# HUP.net
KiCad netlist of a schematic drawn in Altium Designer
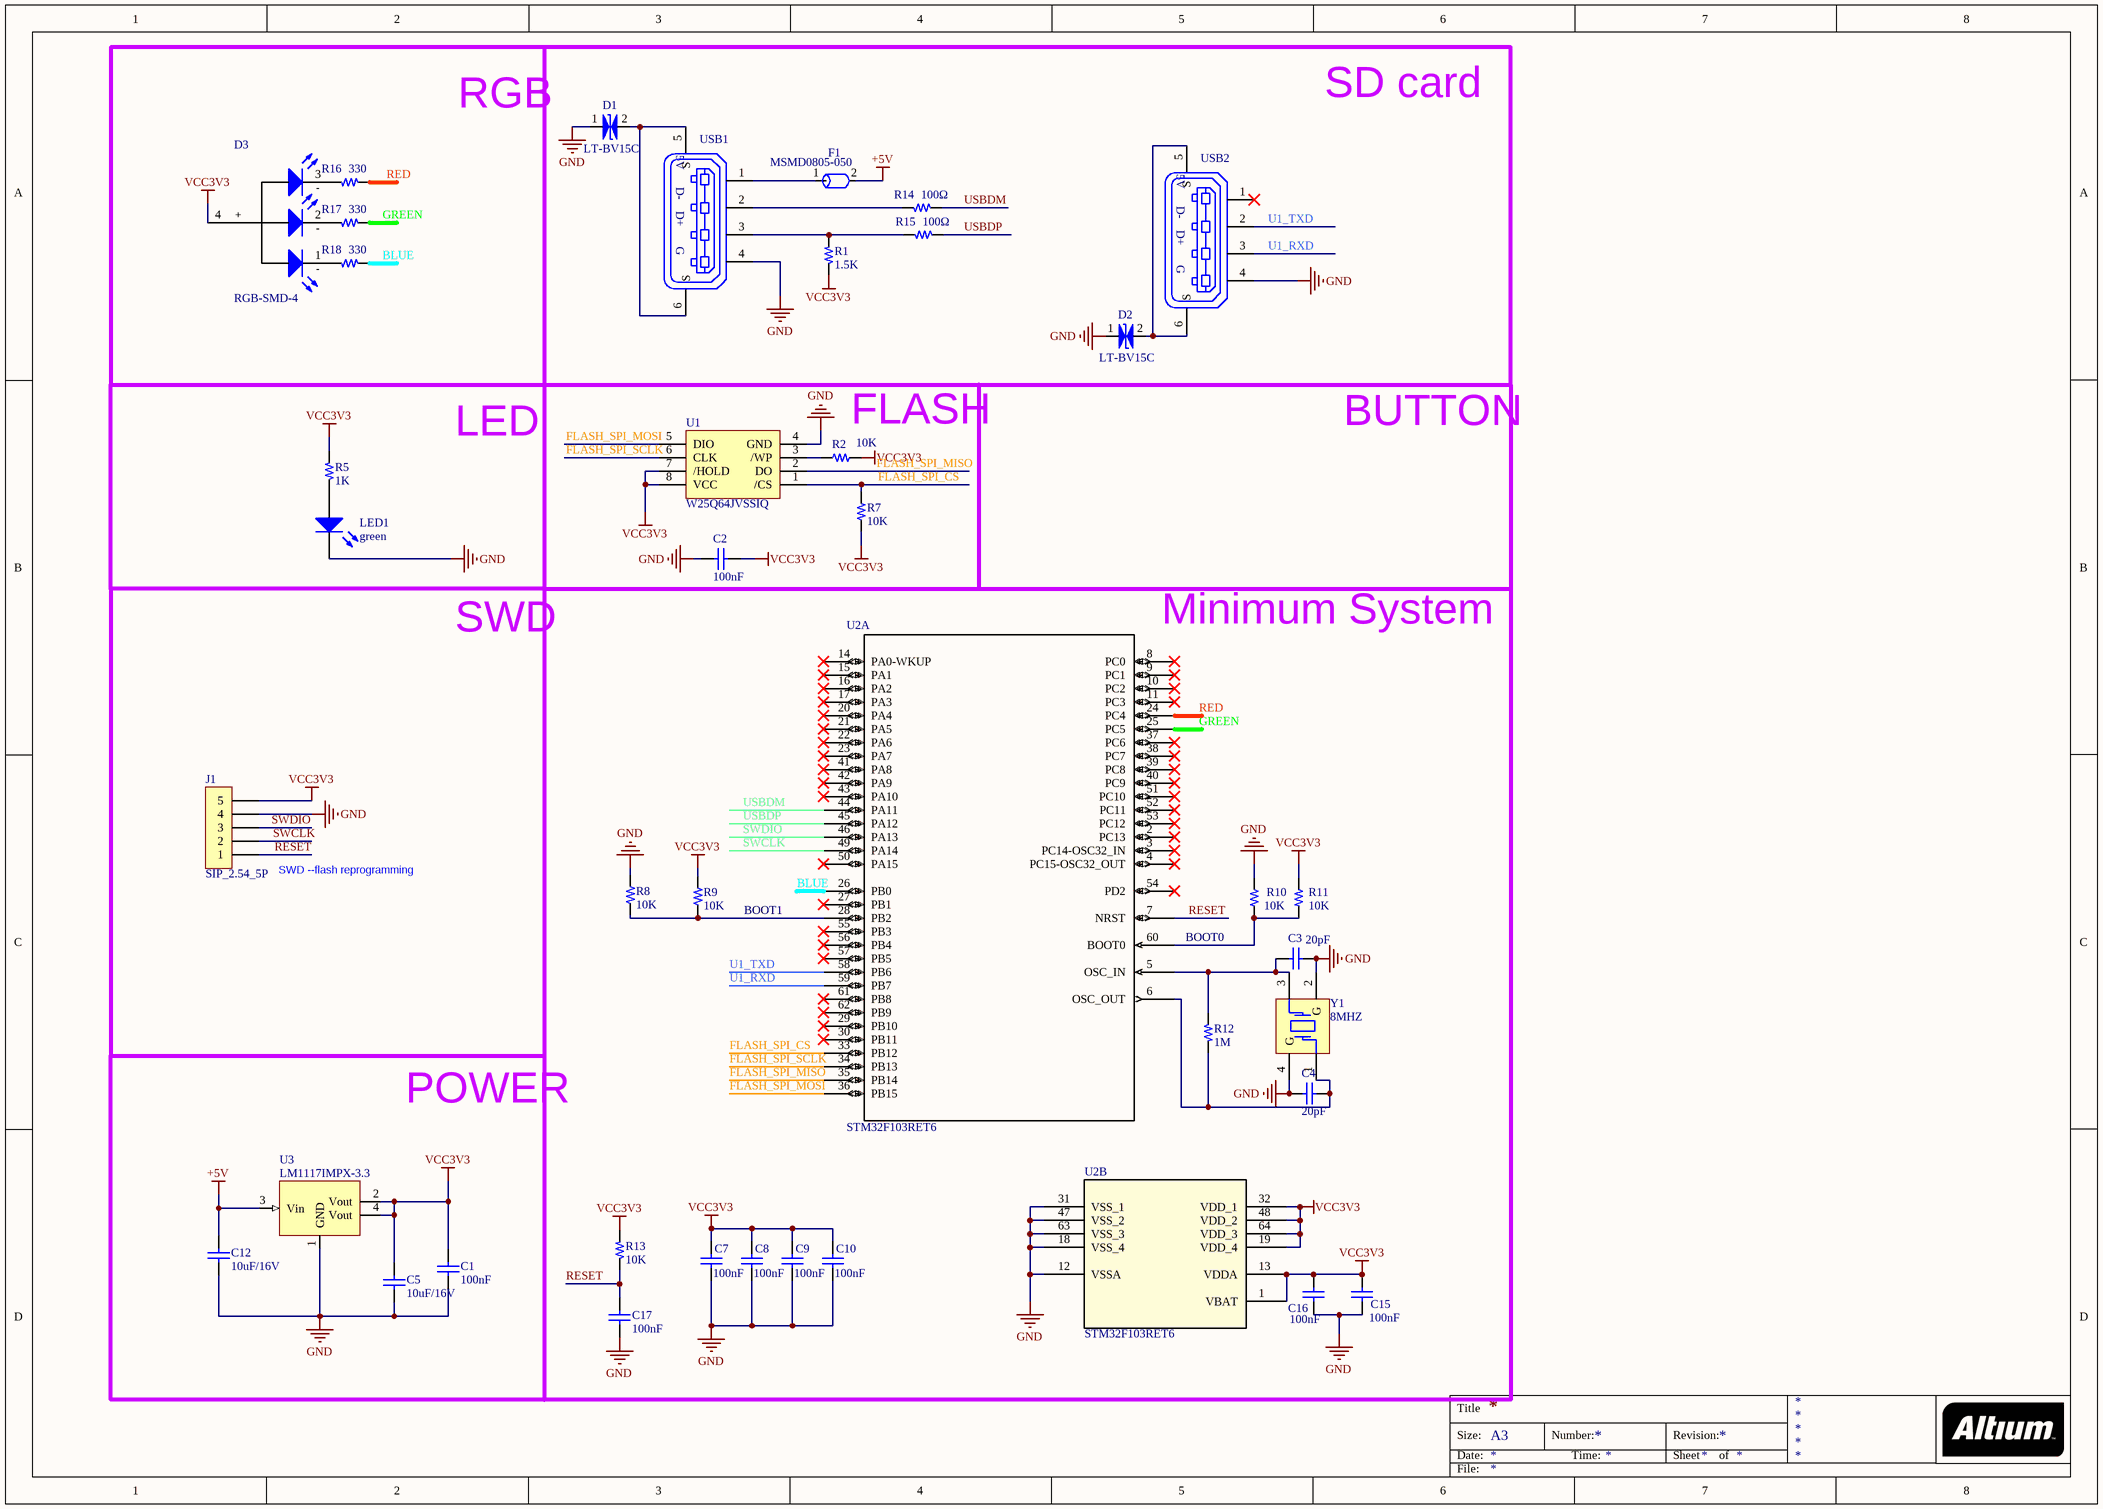
[diagram p0: HUP.SchDoc]

(export (version "E")
  (design (tool "Eeschema 10.0.6"))
  (components
    (comp (ref "C1") (value "100nF") (footprint "C-0603") (libsource (lib "电容") (part "100nF_0805")))
    (comp (ref "C2") (value "100nF") (footprint "C-0603") (libsource (lib "电容") (part "100nF_0805")))
    (comp (ref "C3") (value "20pF") (footprint "C-0603") (libsource (lib "电容") (part "20pF_0805")))
    (comp (ref "C4") (value "20pF") (footprint "C-0603") (libsource (lib "电容") (part "20pF_0805")))
    (comp (ref "C5") (value "10uF/16V") (footprint "C-0603") (libsource (lib "电容") (part "10uF_0805")))
    (comp (ref "C7") (value "100nF") (footprint "C-0603") (libsource (lib "电容") (part "100nF_0805")))
    (comp (ref "C8") (value "100nF") (footprint "C-0603") (libsource (lib "电容") (part "100nF_0805")))
    (comp (ref "C9") (value "100nF") (footprint "C-0603") (libsource (lib "电容") (part "100nF_0805")))
    (comp (ref "C10") (value "100nF") (footprint "C-0603") (libsource (lib "电容") (part "100nF_0805")))
    (comp (ref "C12") (value "10uF/16V") (footprint "C-0603") (libsource (lib "电容") (part "10uF_0805")))
    (comp (ref "C15") (value "100nF") (footprint "C-0603") (libsource (lib "电容") (part "1uF_0805")))
    (comp (ref "C16") (value "100nF") (footprint "C-0603") (libsource (lib "电容") (part "10nF_0805")))
    (comp (ref "C17") (value "100nF") (footprint "C-0603") (libsource (lib "电容") (part "20pF_0805")))
    (comp (ref "D1") (value "LT-BV15C") (footprint "SOD323T") (libsource (lib "临时库") (part "LTBV05C")))
    (comp (ref "D2") (value "LT-BV15C") (footprint "SOD323T") (libsource (lib "临时库") (part "LTBV05C")))
    (comp (ref "D3") (value "RGB-SMD-4") (libsource (lib "Schlib1") (part "RGB")))
    (comp (ref "F1")
      (value "MSMD0805-050")
      (footprint "R0805")
      (libsource (lib "其它") (part "FB_1K/500mA_0805"))
    )
    (comp (ref "J1")
      (value "SIP_2.54_5P")
      (footprint "SIP_2.54_5P")
      (libsource (lib "connectors") (part "SIP_2.54_5P"))
    )
    (comp (ref "LED1") (value "green") (footprint "0603_LED_S1") (libsource (lib "HHFNC") (part "LED1")))
    (comp (ref "R1") (value "1.5K") (footprint "R-0603") (libsource (lib "电阻") (part "10K±1%_0805")))
    (comp (ref "R2") (value "10K") (footprint "R-0603") (libsource (lib "电阻") (part "4.7K±1%_0805")))
    (comp (ref "R5") (value "1K") (footprint "R-0603") (libsource (lib "电阻") (part "1K±1%_0805")))
    (comp (ref "R7") (value "10K") (footprint "R-0603") (libsource (lib "电阻") (part "4.7K±1%_0805")))
    (comp (ref "R8") (value "10K") (footprint "R-0603") (libsource (lib "电阻") (part "10K±1%_0805")))
    (comp (ref "R9") (value "10K") (footprint "R-0603") (libsource (lib "电阻") (part "10K±1%_0805")))
    (comp (ref "R10") (value "10K") (footprint "R-0603") (libsource (lib "电阻") (part "10K±1%_0805")))
    (comp (ref "R11") (value "10K") (footprint "R-0603") (libsource (lib "电阻") (part "10K±1%_0805")))
    (comp (ref "R12") (value "1M") (footprint "R-0603") (libsource (lib "电阻") (part "1M±1%_0805")))
    (comp (ref "R13") (value "10K") (footprint "R-0603") (libsource (lib "电阻") (part "10K±1%_0805")))
    (comp (ref "R14") (value "100Ω") (footprint "R-0603") (libsource (lib "电阻") (part "10K±1%_0805")))
    (comp (ref "R15") (value "100Ω") (footprint "R-0603") (libsource (lib "电阻") (part "10K±1%_0805")))
    (comp (ref "R16") (value "330") (footprint "R-0603") (libsource (lib "电阻") (part "10K±1%_0805")))
    (comp (ref "R17") (value "330") (footprint "R-0603") (libsource (lib "电阻") (part "10K±1%_0805")))
    (comp (ref "R18") (value "330") (footprint "R-0603") (libsource (lib "电阻") (part "10K±1%_0805")))
    (comp (ref "U1")
      (value "W25Q64JVSSIQ")
      (footprint "W25Q64JVSSIQ")
      (libsource (lib "双水平_2") (part "W25Q64JVSSIQ"))
    )
    (comp (ref "U2")
      (value "STM32F103RET6")
      (footprint "LQFP64-10x10mm")
      (description "Imported")
      (fields
        (field (name "MANUFACTURER_PART_NUMBER") "stm32f10xrxt2")
        (field (name "COPYRIGHT") "Copyright (C) 2016 Accelerated Designs. All rights reserved")
      )
      (libsource (lib "2019-01-10_14-16-15") (part "STM32F10xRxT2"))
    )
    (comp (ref "U3")
      (value "LM1117IMPX-3.3")
      (footprint "SOT223")
      (libsource (lib "BLDC_SchLib") (part "LM1117IMPX-3.3"))
    )
    (comp (ref "USB1") (value "USB") (footprint "USB-A-Plug-2") (libsource (lib "双水平_2") (part "USB_A")))
    (comp (ref "USB2") (value "USB") (footprint "USB A Header") (libsource (lib "双水平_2") (part "USB_A")))
    (comp (ref "Y1") (value "8MHZ") (footprint "TAS3225") (libsource (lib "my") (part "泰艺5032晶振8MHz")))
  )
  (nets
    (net (code "1") (name "+5V") (class "Default")
      (node (ref "C12") (pin "1") (pinfunction "1_1") (pintype "passive"))
      (node (ref "F1") (pin "2") (pinfunction "2_2") (pintype "passive"))
      (node (ref "U3") (pin "3") (pinfunction "Vin_3") (pintype "input"))
    )
    (net (code "2") (name "/BLUE") (class "Default")
      (node (ref "R18") (pin "1") (pinfunction "TOP_1") (pintype "passive"))
      (node (ref "U2") (pin "26") (pinfunction "PB0_26") (pintype "bidirectional"))
    )
    (net (code "3") (name "/BOOT0") (class "Default")
      (node (ref "R10") (pin "2") (pinfunction "BOT_2") (pintype "passive"))
      (node (ref "R11") (pin "2") (pinfunction "BOT_2") (pintype "passive"))
      (node (ref "U2") (pin "60") (pinfunction "BOOT0_60") (pintype "input"))
    )
    (net (code "4") (name "/BOOT1") (class "Default")
      (node (ref "R8") (pin "2") (pinfunction "BOT_2") (pintype "passive"))
      (node (ref "R9") (pin "2") (pinfunction "BOT_2") (pintype "passive"))
      (node (ref "U2") (pin "28") (pinfunction "PB2_28") (pintype "bidirectional"))
    )
    (net (code "5") (name "/FLASH_SPI_CS") (class "Default")
      (node (ref "R7") (pin "2") (pinfunction "BOT_2") (pintype "passive"))
      (node (ref "U1") (pin "1") (pinfunction "/CS_1") (pintype "passive"))
      (node (ref "U2") (pin "33") (pinfunction "PB12_33") (pintype "bidirectional"))
    )
    (net (code "6") (name "/FLASH_SPI_MISO") (class "Default")
      (node (ref "U1") (pin "2") (pinfunction "DO_2") (pintype "passive"))
      (node (ref "U2") (pin "35") (pinfunction "PB14_35") (pintype "bidirectional"))
    )
    (net (code "7") (name "/FLASH_SPI_MOSI") (class "Default")
      (node (ref "U1") (pin "5") (pinfunction "DIO_5") (pintype "passive"))
      (node (ref "U2") (pin "36") (pinfunction "PB15_36") (pintype "bidirectional"))
    )
    (net (code "8") (name "/FLASH_SPI_SCLK") (class "Default")
      (node (ref "U1") (pin "6") (pinfunction "CLK_6") (pintype "passive"))
      (node (ref "U2") (pin "34") (pinfunction "PB13_34") (pintype "bidirectional"))
    )
    (net (code "9") (name "/GREEN") (class "Default")
      (node (ref "R17") (pin "1") (pinfunction "TOP_1") (pintype "passive"))
      (node (ref "U2") (pin "25") (pinfunction "PC5_25") (pintype "bidirectional"))
    )
    (net (code "10") (name "/RED") (class "Default")
      (node (ref "R16") (pin "1") (pinfunction "TOP_1") (pintype "passive"))
      (node (ref "U2") (pin "24") (pinfunction "PC4_24") (pintype "bidirectional"))
    )
    (net (code "11") (name "/RESET") (class "Default")
      (node (ref "C17") (pin "1") (pinfunction "1_1") (pintype "passive"))
      (node (ref "J1") (pin "1") (pinfunction "1_1") (pintype "passive"))
      (node (ref "R13") (pin "1") (pinfunction "TOP_1") (pintype "passive"))
      (node (ref "U2") (pin "7") (pinfunction "NRST_7") (pintype "bidirectional"))
    )
    (net (code "12") (name "/SWCLK") (class "Default")
      (node (ref "J1") (pin "2") (pinfunction "2_2") (pintype "passive"))
      (node (ref "U2") (pin "49") (pinfunction "PA14_49") (pintype "bidirectional"))
    )
    (net (code "13") (name "/SWDIO") (class "Default")
      (node (ref "J1") (pin "3") (pinfunction "3_3") (pintype "passive"))
      (node (ref "U2") (pin "46") (pinfunction "PA13_46") (pintype "bidirectional"))
    )
    (net (code "14") (name "/U1_RXD") (class "Default")
      (node (ref "U2") (pin "59") (pinfunction "PB7_59") (pintype "bidirectional"))
      (node (ref "USB2") (pin "3") (pinfunction "3_3") (pintype "passive"))
    )
    (net (code "15") (name "/U1_TXD") (class "Default")
      (node (ref "U2") (pin "58") (pinfunction "PB6_58") (pintype "bidirectional"))
      (node (ref "USB2") (pin "2") (pinfunction "2_2") (pintype "passive"))
    )
    (net (code "16") (name "/USBDM") (class "Default")
      (node (ref "R14") (pin "1") (pinfunction "TOP_1") (pintype "passive"))
      (node (ref "U2") (pin "44") (pinfunction "PA11_44") (pintype "bidirectional"))
    )
    (net (code "17") (name "/USBDP") (class "Default")
      (node (ref "R15") (pin "1") (pinfunction "TOP_1") (pintype "passive"))
      (node (ref "U2") (pin "45") (pinfunction "PA12_45") (pintype "bidirectional"))
    )
    (net (code "18") (name "GND") (class "Default")
      (node (ref "C1") (pin "1") (pinfunction "1_1") (pintype "passive"))
      (node (ref "C10") (pin "1") (pinfunction "1_1") (pintype "passive"))
      (node (ref "C12") (pin "2") (pinfunction "2_2") (pintype "passive"))
      (node (ref "C15") (pin "2") (pinfunction "2_2") (pintype "passive"))
      (node (ref "C16") (pin "1") (pinfunction "1_1") (pintype "passive"))
      (node (ref "C17") (pin "2") (pinfunction "2_2") (pintype "passive"))
      (node (ref "C2") (pin "2") (pinfunction "2_2") (pintype "passive"))
      (node (ref "C3") (pin "1") (pinfunction "1_1") (pintype "passive"))
      (node (ref "C4") (pin "2") (pinfunction "2_2") (pintype "passive"))
      (node (ref "C5") (pin "2") (pinfunction "2_2") (pintype "passive"))
      (node (ref "C7") (pin "1") (pinfunction "1_1") (pintype "passive"))
      (node (ref "C8") (pin "1") (pinfunction "1_1") (pintype "passive"))
      (node (ref "C9") (pin "1") (pinfunction "1_1") (pintype "passive"))
      (node (ref "D1") (pin "1") (pinfunction "1_1") (pintype "passive"))
      (node (ref "D2") (pin "1") (pinfunction "1_1") (pintype "passive"))
      (node (ref "J1") (pin "4") (pinfunction "4_4") (pintype "passive"))
      (node (ref "LED1") (pin "2") (pinfunction "K_2") (pintype "passive"))
      (node (ref "R10") (pin "1") (pinfunction "TOP_1") (pintype "passive"))
      (node (ref "R8") (pin "1") (pinfunction "TOP_1") (pintype "passive"))
      (node (ref "U1") (pin "4") (pinfunction "GND_4") (pintype "passive"))
      (node (ref "U2") (pin "12") (pinfunction "VSSA_12") (pintype "power_in"))
      (node (ref "U2") (pin "18") (pinfunction "VSS_4_18") (pintype "power_in"))
      (node (ref "U2") (pin "31") (pinfunction "VSS_1_31") (pintype "power_in"))
      (node (ref "U2") (pin "47") (pinfunction "VSS_2_47") (pintype "power_in"))
      (node (ref "U2") (pin "63") (pinfunction "VSS_3_63") (pintype "power_in"))
      (node (ref "U3") (pin "1") (pinfunction "GND_1") (pintype "passive"))
      (node (ref "USB1") (pin "4") (pinfunction "4_4") (pintype "passive"))
      (node (ref "USB2") (pin "4") (pinfunction "4_4") (pintype "passive"))
      (node (ref "Y1") (pin "2") (pinfunction "G_2") (pintype "passive"))
      (node (ref "Y1") (pin "4") (pinfunction "G_4") (pintype "passive"))
    )
    (net (code "19") (name "Net-(D1-Pad2)") (class "Default")
      (node (ref "D1") (pin "2") (pinfunction "2_2") (pintype "passive"))
      (node (ref "USB1") (pin "5") (pinfunction "S_5") (pintype "passive"))
      (node (ref "USB1") (pin "6") (pinfunction "S_6") (pintype "passive"))
    )
    (net (code "20") (name "Net-(D2-Pad2)") (class "Default")
      (node (ref "D2") (pin "2") (pinfunction "2_2") (pintype "passive"))
      (node (ref "USB2") (pin "5") (pinfunction "S_5") (pintype "passive"))
      (node (ref "USB2") (pin "6") (pinfunction "S_6") (pintype "passive"))
    )
    (net (code "21") (name "Net-(F1-Pad1)") (class "Default")
      (node (ref "F1") (pin "1") (pinfunction "1_1") (pintype "passive"))
      (node (ref "USB1") (pin "1") (pinfunction "1_1") (pintype "passive"))
    )
    (net (code "22") (name "Net-(LED1-A)") (class "Default")
      (node (ref "LED1") (pin "1") (pinfunction "A_1") (pintype "passive"))
      (node (ref "R5") (pin "1") (pinfunction "TOP_1") (pintype "passive"))
    )
    (net (code "23") (name "Net-(R1-BOT)") (class "Default")
      (node (ref "R1") (pin "2") (pinfunction "BOT_2") (pintype "passive"))
      (node (ref "R15") (pin "2") (pinfunction "BOT_2") (pintype "passive"))
      (node (ref "USB1") (pin "3") (pinfunction "3_3") (pintype "passive"))
    )
    (net (code "24") (name "Net-(R2-BOT)") (class "Default")
      (node (ref "R2") (pin "2") (pinfunction "BOT_2") (pintype "passive"))
      (node (ref "U1") (pin "3") (pinfunction "/WP_3") (pintype "passive"))
    )
    (net (code "25") (name "Net-(R12-BOT)") (class "Default")
      (node (ref "C3") (pin "2") (pinfunction "2_2") (pintype "passive"))
      (node (ref "R12") (pin "2") (pinfunction "BOT_2") (pintype "passive"))
      (node (ref "U2") (pin "5") (pinfunction "OSC_IN_5") (pintype "input"))
      (node (ref "Y1") (pin "3") (pinfunction "3_3") (pintype "passive"))
    )
    (net (code "26") (name "Net-(R12-TOP)") (class "Default")
      (node (ref "C4") (pin "1") (pinfunction "1_1") (pintype "passive"))
      (node (ref "R12") (pin "1") (pinfunction "TOP_1") (pintype "passive"))
      (node (ref "U2") (pin "6") (pinfunction "OSC_OUT_6") (pintype "output"))
      (node (ref "Y1") (pin "1") (pinfunction "1_1") (pintype "passive"))
    )
    (net (code "27") (name "Net-(R14-BOT)") (class "Default")
      (node (ref "R14") (pin "2") (pinfunction "BOT_2") (pintype "passive"))
      (node (ref "USB1") (pin "2") (pinfunction "2_2") (pintype "passive"))
    )
    (net (code "28") (name "Net-(R16-BOT)") (class "Default")
      (node (ref "D3") (pin "3") (pinfunction "3_3") (pintype "passive"))
      (node (ref "R16") (pin "2") (pinfunction "BOT_2") (pintype "passive"))
    )
    (net (code "29") (name "Net-(R17-BOT)") (class "Default")
      (node (ref "D3") (pin "2") (pinfunction "2_2") (pintype "passive"))
      (node (ref "R17") (pin "2") (pinfunction "BOT_2") (pintype "passive"))
    )
    (net (code "30") (name "Net-(R18-BOT)") (class "Default")
      (node (ref "D3") (pin "1") (pinfunction "1_1") (pintype "passive"))
      (node (ref "R18") (pin "2") (pinfunction "BOT_2") (pintype "passive"))
    )
    (net (code "31") (name "VCC3V3") (class "Default")
      (node (ref "C1") (pin "2") (pinfunction "2_2") (pintype "passive"))
      (node (ref "C10") (pin "2") (pinfunction "2_2") (pintype "passive"))
      (node (ref "C15") (pin "1") (pinfunction "1_1") (pintype "passive"))
      (node (ref "C16") (pin "2") (pinfunction "2_2") (pintype "passive"))
      (node (ref "C2") (pin "1") (pinfunction "1_1") (pintype "passive"))
      (node (ref "C5") (pin "1") (pinfunction "1_1") (pintype "passive"))
      (node (ref "C7") (pin "2") (pinfunction "2_2") (pintype "passive"))
      (node (ref "C8") (pin "2") (pinfunction "2_2") (pintype "passive"))
      (node (ref "C9") (pin "2") (pinfunction "2_2") (pintype "passive"))
      (node (ref "D3") (pin "4") (pinfunction "4_4") (pintype "passive"))
      (node (ref "J1") (pin "5") (pinfunction "5_5") (pintype "passive"))
      (node (ref "R1") (pin "1") (pinfunction "TOP_1") (pintype "passive"))
      (node (ref "R11") (pin "1") (pinfunction "TOP_1") (pintype "passive"))
      (node (ref "R13") (pin "2") (pinfunction "BOT_2") (pintype "passive"))
      (node (ref "R2") (pin "1") (pinfunction "TOP_1") (pintype "passive"))
      (node (ref "R5") (pin "2") (pinfunction "BOT_2") (pintype "passive"))
      (node (ref "R7") (pin "1") (pinfunction "TOP_1") (pintype "passive"))
      (node (ref "R9") (pin "1") (pinfunction "TOP_1") (pintype "passive"))
      (node (ref "U1") (pin "7") (pinfunction "/HOLD_7") (pintype "passive"))
      (node (ref "U1") (pin "8") (pinfunction "VCC_8") (pintype "passive"))
      (node (ref "U2") (pin "1") (pinfunction "VBAT_1") (pintype "power_in"))
      (node (ref "U2") (pin "13") (pinfunction "VDDA_13") (pintype "power_in"))
      (node (ref "U2") (pin "19") (pinfunction "VDD_4_19") (pintype "power_in"))
      (node (ref "U2") (pin "32") (pinfunction "VDD_1_32") (pintype "power_in"))
      (node (ref "U2") (pin "48") (pinfunction "VDD_2_48") (pintype "power_in"))
      (node (ref "U2") (pin "64") (pinfunction "VDD_3_64") (pintype "power_in"))
      (node (ref "U3") (pin "2") (pinfunction "Vout_2") (pintype "passive"))
      (node (ref "U3") (pin "4") (pinfunction "Vout_4") (pintype "passive"))
    )
    (net (code "32") (name "unconnected-(U2A-PA0-WKUP-Pad14)") (class "Default")
      (node (ref "U2") (pin "14") (pinfunction "PA0-WKUP_14") (pintype "bidirectional+no_connect"))
    )
    (net (code "33") (name "unconnected-(U2A-PA1-Pad15)") (class "Default")
      (node (ref "U2") (pin "15") (pinfunction "PA1_15") (pintype "bidirectional+no_connect"))
    )
    (net (code "34") (name "unconnected-(U2A-PA2-Pad16)") (class "Default")
      (node (ref "U2") (pin "16") (pinfunction "PA2_16") (pintype "bidirectional+no_connect"))
    )
    (net (code "35") (name "unconnected-(U2A-PA3-Pad17)") (class "Default")
      (node (ref "U2") (pin "17") (pinfunction "PA3_17") (pintype "bidirectional+no_connect"))
    )
    (net (code "36") (name "unconnected-(U2A-PA4-Pad20)") (class "Default")
      (node (ref "U2") (pin "20") (pinfunction "PA4_20") (pintype "bidirectional+no_connect"))
    )
    (net (code "37") (name "unconnected-(U2A-PA5-Pad21)") (class "Default")
      (node (ref "U2") (pin "21") (pinfunction "PA5_21") (pintype "bidirectional+no_connect"))
    )
    (net (code "38") (name "unconnected-(U2A-PA6-Pad22)") (class "Default")
      (node (ref "U2") (pin "22") (pinfunction "PA6_22") (pintype "bidirectional+no_connect"))
    )
    (net (code "39") (name "unconnected-(U2A-PA7-Pad23)") (class "Default")
      (node (ref "U2") (pin "23") (pinfunction "PA7_23") (pintype "bidirectional+no_connect"))
    )
    (net (code "40") (name "unconnected-(U2A-PA8-Pad41)") (class "Default")
      (node (ref "U2") (pin "41") (pinfunction "PA8_41") (pintype "bidirectional+no_connect"))
    )
    (net (code "41") (name "unconnected-(U2A-PA9-Pad42)") (class "Default")
      (node (ref "U2") (pin "42") (pinfunction "PA9_42") (pintype "bidirectional+no_connect"))
    )
    (net (code "42") (name "unconnected-(U2A-PA10-Pad43)") (class "Default")
      (node (ref "U2") (pin "43") (pinfunction "PA10_43") (pintype "bidirectional+no_connect"))
    )
    (net (code "43") (name "unconnected-(U2A-PA15-Pad50)") (class "Default")
      (node (ref "U2") (pin "50") (pinfunction "PA15_50") (pintype "bidirectional+no_connect"))
    )
    (net (code "44") (name "unconnected-(U2A-PB1-Pad27)") (class "Default")
      (node (ref "U2") (pin "27") (pinfunction "PB1_27") (pintype "bidirectional+no_connect"))
    )
    (net (code "45") (name "unconnected-(U2A-PB3-Pad55)") (class "Default")
      (node (ref "U2") (pin "55") (pinfunction "PB3_55") (pintype "bidirectional+no_connect"))
    )
    (net (code "46") (name "unconnected-(U2A-PB4-Pad56)") (class "Default")
      (node (ref "U2") (pin "56") (pinfunction "PB4_56") (pintype "bidirectional+no_connect"))
    )
    (net (code "47") (name "unconnected-(U2A-PB5-Pad57)") (class "Default")
      (node (ref "U2") (pin "57") (pinfunction "PB5_57") (pintype "bidirectional+no_connect"))
    )
    (net (code "48") (name "unconnected-(U2A-PB8-Pad61)") (class "Default")
      (node (ref "U2") (pin "61") (pinfunction "PB8_61") (pintype "bidirectional+no_connect"))
    )
    (net (code "49") (name "unconnected-(U2A-PB9-Pad62)") (class "Default")
      (node (ref "U2") (pin "62") (pinfunction "PB9_62") (pintype "bidirectional+no_connect"))
    )
    (net (code "50") (name "unconnected-(U2A-PB10-Pad29)") (class "Default")
      (node (ref "U2") (pin "29") (pinfunction "PB10_29") (pintype "bidirectional+no_connect"))
    )
    (net (code "51") (name "unconnected-(U2A-PB11-Pad30)") (class "Default")
      (node (ref "U2") (pin "30") (pinfunction "PB11_30") (pintype "bidirectional+no_connect"))
    )
    (net (code "52") (name "unconnected-(U2A-PC0-Pad8)") (class "Default")
      (node (ref "U2") (pin "8") (pinfunction "PC0_8") (pintype "bidirectional+no_connect"))
    )
    (net (code "53") (name "unconnected-(U2A-PC1-Pad9)") (class "Default")
      (node (ref "U2") (pin "9") (pinfunction "PC1_9") (pintype "bidirectional+no_connect"))
    )
    (net (code "54") (name "unconnected-(U2A-PC2-Pad10)") (class "Default")
      (node (ref "U2") (pin "10") (pinfunction "PC2_10") (pintype "bidirectional+no_connect"))
    )
    (net (code "55") (name "unconnected-(U2A-PC3-Pad11)") (class "Default")
      (node (ref "U2") (pin "11") (pinfunction "PC3_11") (pintype "bidirectional+no_connect"))
    )
    (net (code "56") (name "unconnected-(U2A-PC6-Pad37)") (class "Default")
      (node (ref "U2") (pin "37") (pinfunction "PC6_37") (pintype "bidirectional+no_connect"))
    )
    (net (code "57") (name "unconnected-(U2A-PC7-Pad38)") (class "Default")
      (node (ref "U2") (pin "38") (pinfunction "PC7_38") (pintype "bidirectional+no_connect"))
    )
    (net (code "58") (name "unconnected-(U2A-PC8-Pad39)") (class "Default")
      (node (ref "U2") (pin "39") (pinfunction "PC8_39") (pintype "bidirectional+no_connect"))
    )
    (net (code "59") (name "unconnected-(U2A-PC9-Pad40)") (class "Default")
      (node (ref "U2") (pin "40") (pinfunction "PC9_40") (pintype "bidirectional+no_connect"))
    )
    (net (code "60") (name "unconnected-(U2A-PC10-Pad51)") (class "Default")
      (node (ref "U2") (pin "51") (pinfunction "PC10_51") (pintype "bidirectional+no_connect"))
    )
    (net (code "61") (name "unconnected-(U2A-PC11-Pad52)") (class "Default")
      (node (ref "U2") (pin "52") (pinfunction "PC11_52") (pintype "bidirectional+no_connect"))
    )
    (net (code "62") (name "unconnected-(U2A-PC12-Pad53)") (class "Default")
      (node (ref "U2") (pin "53") (pinfunction "PC12_53") (pintype "bidirectional+no_connect"))
    )
    (net (code "63") (name "unconnected-(U2A-PC13-Pad2)") (class "Default")
      (node (ref "U2") (pin "2") (pinfunction "PC13_2") (pintype "bidirectional+no_connect"))
    )
    (net (code "64") (name "unconnected-(U2A-PC14-OSC32_IN-Pad3)") (class "Default")
      (node (ref "U2") (pin "3") (pinfunction "PC14-OSC32_IN_3") (pintype "bidirectional+no_connect"))
    )
    (net (code "65") (name "unconnected-(U2A-PC15-OSC32_OUT-Pad4)") (class "Default")
      (node (ref "U2") (pin "4") (pinfunction "PC15-OSC32_OUT_4") (pintype "bidirectional+no_connect"))
    )
    (net (code "66") (name "unconnected-(U2A-PD2-Pad54)") (class "Default")
      (node (ref "U2") (pin "54") (pinfunction "PD2_54") (pintype "bidirectional+no_connect"))
    )
    (net (code "67") (name "unconnected-(USB2-Pad1)") (class "Default")
      (node (ref "USB2") (pin "1") (pinfunction "1_1") (pintype "passive+no_connect"))
    )
  )
)
